# Microcontroller.net
KiCad netlist of a schematic drawn in Altium Designer
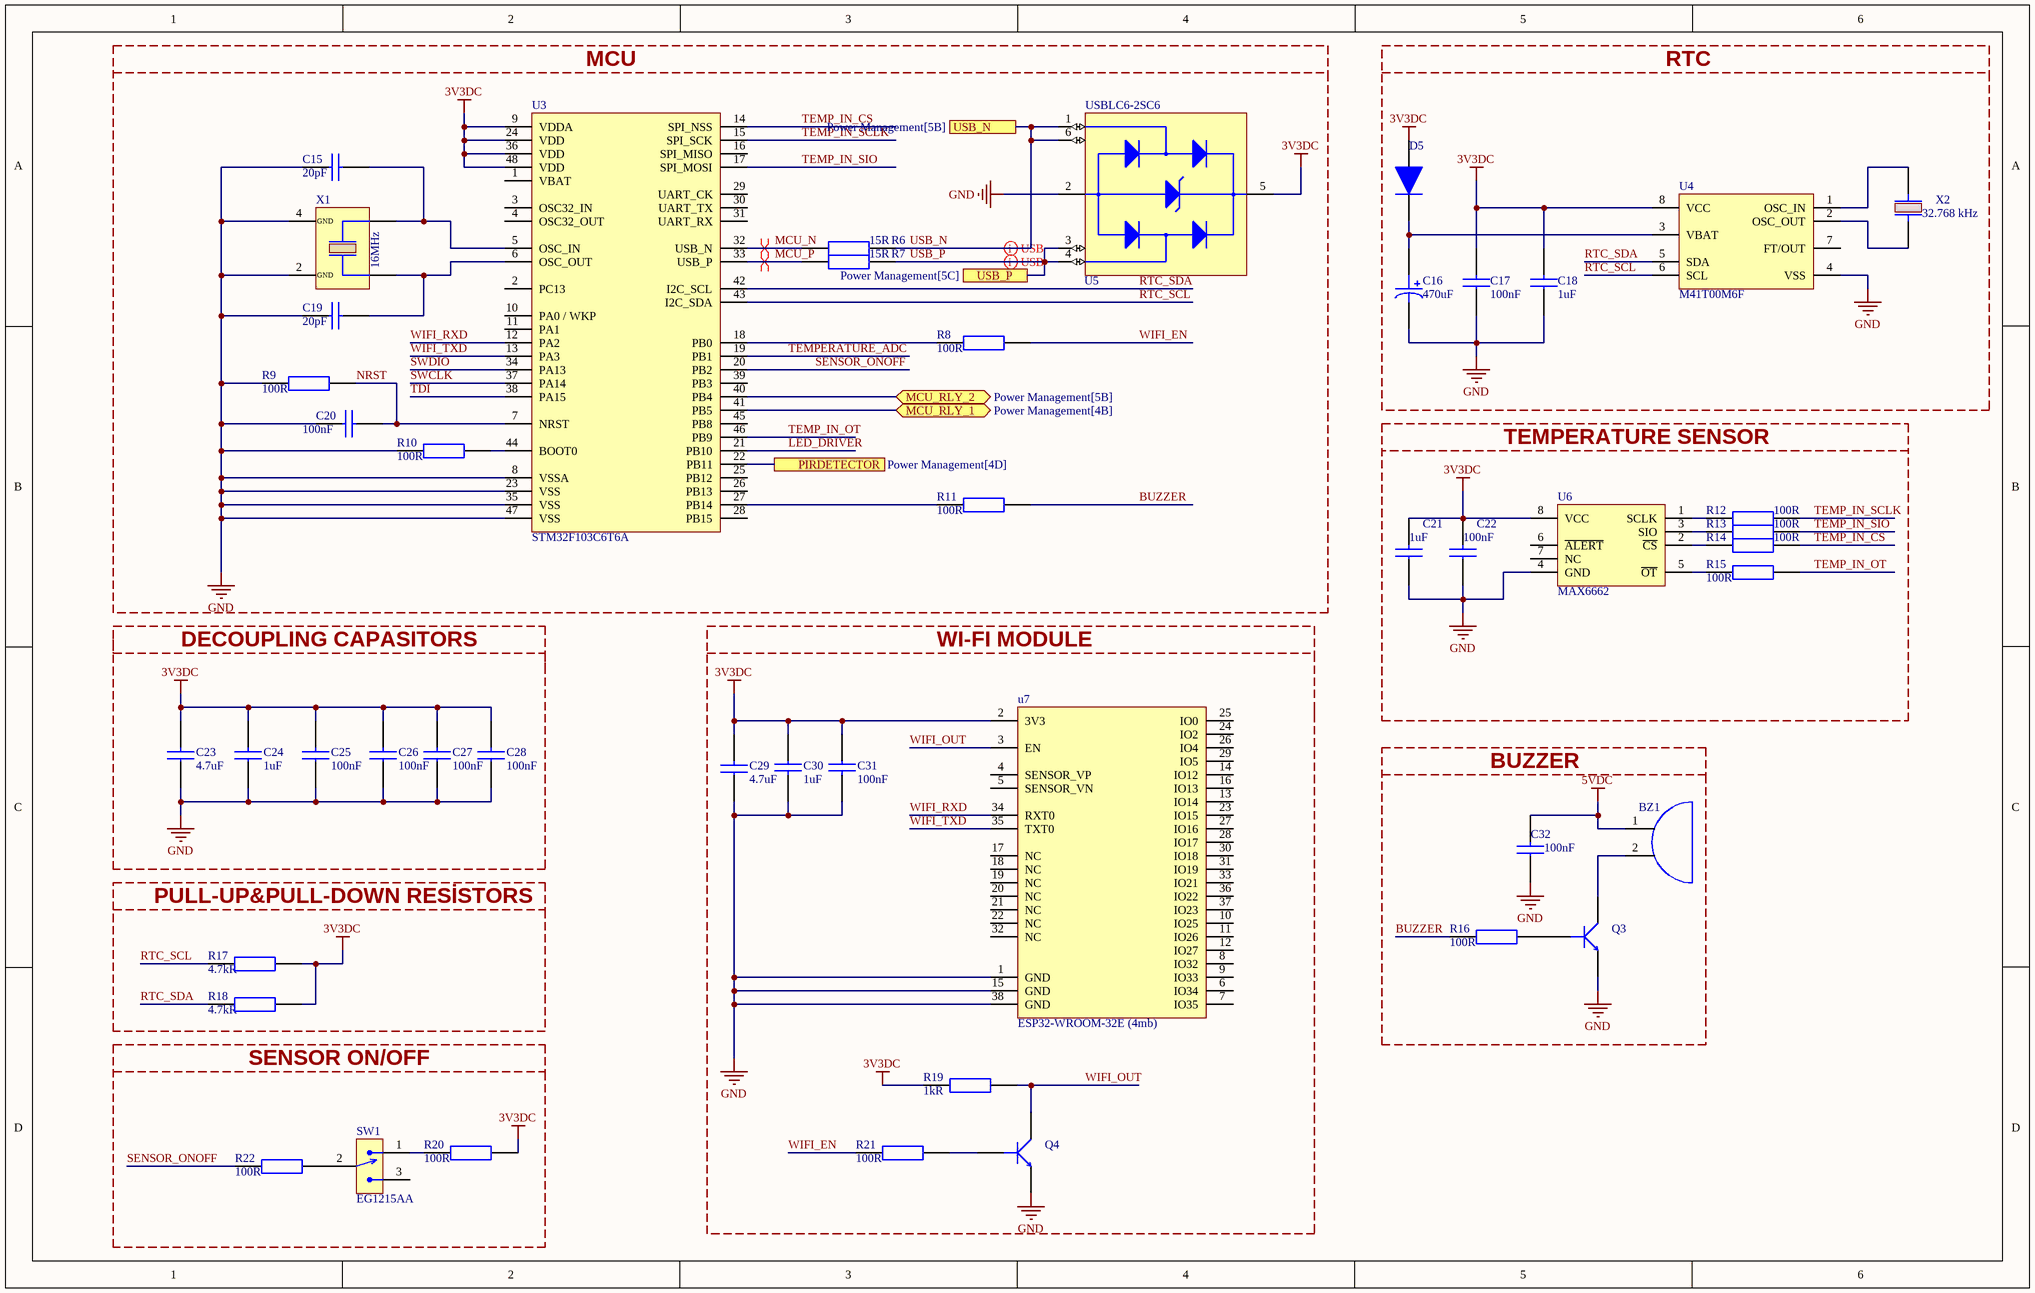
[diagram p0: Microcontroller.SchDoc]

(export (version "E")
  (design (tool "Eeschema 10.0.6"))
  (components
    (comp (ref "BZ1")
      (value "CMI-9605IC-0580T")
      (footprint "CMI-9605IC")
      (description "Audio Buzzer Magnetic 3VDC 7VDC 30mA 5VDC 85dB 2600Hz to 2800Hz Through Hole Pin Box")
      (fields (field (name "MANUFACTURER") "CUI Devices") (field (name "DESIGNED BY") "Mustafa"))
      (libsource (lib "Mustafa_Library") (part "CMI-9605IC-0580T"))
    )
    (comp (ref "C15")
      (value "CL10C200JB8NNNC")
      (footprint "CAP_0603")
      (description "CAP CER 20pF %5 0603 SMD")
      (fields
        (field (name "MANUFACTURER") "Samsung")
        (field (name "TOLERANCE") "5%")
        (field (name "CAPACITANCE") "20pF")
        (field (name "DESIGNED BY") "Mustafa")
      )
      (libsource (lib "Mustafa_Library") (part "CAP CER 20pF 0603"))
    )
    (comp (ref "C16")
      (value "ESH477M050AH4AA")
      (footprint "CAP_RADIAL_D10_P5")
      (description "CAP ALU ELEC 470uF 50V RADIAL")
      (fields
        (field (name "MANUFACTURER") "KEMET")
        (field (name "TOLERANCE") "20%")
        (field (name "CAPACITANCE") "470uF")
        (field (name "DESIGNED BY") "BERK")
      )
      (libsource (lib "Mustafa_Library") (part "CAP ALU ELEC 470uF 50V"))
    )
    (comp (ref "C17")
      (value "CL21B104KBCNNNC")
      (footprint "CAP_0805")
      (description "CAP CER 100nF %10 0805")
      (fields
        (field (name "MANUFACTURER") "Samsung")
        (field (name "TOLERANCE") "10%")
        (field (name "CAPACITANCE") "100nF")
        (field (name "DESIGNED BY") "Mustafa")
      )
      (libsource (lib "Mustafa_Library") (part "CAP CER 100nF 0805"))
    )
    (comp (ref "C18")
      (value "CL21B105KBFNNNE")
      (footprint "CAP_0805")
      (description "CAP CER 1uF %10 0805")
      (fields
        (field (name "MANUFACTURER") "Samsung")
        (field (name "TOLERANCE") "10%")
        (field (name "CAPACITANCE") "1uF")
        (field (name "DESIGNED BY") "Mustafa")
      )
      (libsource (lib "Mustafa_Library") (part "CAP CER 1uF 0805"))
    )
    (comp (ref "C19")
      (value "CL10C200JB8NNNC")
      (footprint "CAP_0603")
      (description "CAP CER 20pF %5 0603 SMD")
      (fields
        (field (name "MANUFACTURER") "Samsung")
        (field (name "TOLERANCE") "5%")
        (field (name "CAPACITANCE") "20pF")
        (field (name "DESIGNED BY") "Mustafa")
      )
      (libsource (lib "Mustafa_Library") (part "CAP CER 20pF 0603"))
    )
    (comp (ref "C20")
      (value "CL21B104KBCNNNC")
      (footprint "CAP_0805")
      (description "CAP CER 100nF %10 0805")
      (fields
        (field (name "MANUFACTURER") "Samsung")
        (field (name "TOLERANCE") "10%")
        (field (name "CAPACITANCE") "100nF")
        (field (name "DESIGNED BY") "Mustafa")
      )
      (libsource (lib "Mustafa_Library") (part "CAP CER 100nF 0805"))
    )
    (comp (ref "C21")
      (value "CL21B105KBFNNNE")
      (footprint "CAP_0805")
      (description "CAP CER 1uF %10 0805")
      (fields
        (field (name "MANUFACTURER") "Samsung")
        (field (name "TOLERANCE") "10%")
        (field (name "CAPACITANCE") "1uF")
        (field (name "DESIGNED BY") "Mustafa")
      )
      (libsource (lib "Mustafa_Library") (part "CAP CER 1uF 0805"))
    )
    (comp (ref "C22")
      (value "CL21B104KBCNNNC")
      (footprint "CAP_0805")
      (description "CAP CER 100nF %10 0805")
      (fields
        (field (name "MANUFACTURER") "Samsung")
        (field (name "TOLERANCE") "10%")
        (field (name "CAPACITANCE") "100nF")
        (field (name "DESIGNED BY") "Mustafa")
      )
      (libsource (lib "Mustafa_Library") (part "CAP CER 100nF 0805"))
    )
    (comp (ref "C23")
      (value "CL21A475KAQNNNE")
      (footprint "CAP_0805")
      (description "CAP CER 4.7uF %10 0805")
      (fields
        (field (name "MANUFACTURER") "Samsung")
        (field (name "TOLERANCE") "10%")
        (field (name "CAPACITANCE") "4.7uF")
        (field (name "DESIGNED BY") "Mustafa")
      )
      (libsource (lib "Mustafa_Library") (part "CAP CER 4.7uF 0805"))
    )
    (comp (ref "C24")
      (value "CL21B105KBFNNNE")
      (footprint "CAP_0805")
      (description "CAP CER 1uF %10 0805")
      (fields
        (field (name "MANUFACTURER") "Samsung")
        (field (name "TOLERANCE") "10%")
        (field (name "CAPACITANCE") "1uF")
        (field (name "DESIGNED BY") "Mustafa")
      )
      (libsource (lib "Mustafa_Library") (part "CAP CER 1uF 0805"))
    )
    (comp (ref "C25")
      (value "CL21B104KBCNNNC")
      (footprint "CAP_0805")
      (description "CAP CER 100nF %10 0805")
      (fields
        (field (name "MANUFACTURER") "Samsung")
        (field (name "TOLERANCE") "10%")
        (field (name "CAPACITANCE") "100nF")
        (field (name "DESIGNED BY") "Mustafa")
      )
      (libsource (lib "Mustafa_Library") (part "CAP CER 100nF 0805"))
    )
    (comp (ref "C26")
      (value "CL21B104KBCNNNC")
      (footprint "CAP_0805")
      (description "CAP CER 100nF %10 0805")
      (fields
        (field (name "MANUFACTURER") "Samsung")
        (field (name "TOLERANCE") "10%")
        (field (name "CAPACITANCE") "100nF")
        (field (name "DESIGNED BY") "Mustafa")
      )
      (libsource (lib "Mustafa_Library") (part "CAP CER 100nF 0805"))
    )
    (comp (ref "C27")
      (value "CL21B104KBCNNNC")
      (footprint "CAP_0805")
      (description "CAP CER 100nF %10 0805")
      (fields
        (field (name "MANUFACTURER") "Samsung")
        (field (name "TOLERANCE") "10%")
        (field (name "CAPACITANCE") "100nF")
        (field (name "DESIGNED BY") "Mustafa")
      )
      (libsource (lib "Mustafa_Library") (part "CAP CER 100nF 0805"))
    )
    (comp (ref "C28")
      (value "CL21B104KBCNNNC")
      (footprint "CAP_0805")
      (description "CAP CER 100nF %10 0805")
      (fields
        (field (name "MANUFACTURER") "Samsung")
        (field (name "TOLERANCE") "10%")
        (field (name "CAPACITANCE") "100nF")
        (field (name "DESIGNED BY") "Mustafa")
      )
      (libsource (lib "Mustafa_Library") (part "CAP CER 100nF 0805"))
    )
    (comp (ref "C29")
      (value "CL21A475KAQNNNE")
      (footprint "CAP_0805")
      (description "CAP CER 4.7uF %10 0805")
      (fields
        (field (name "MANUFACTURER") "Samsung")
        (field (name "TOLERANCE") "10%")
        (field (name "CAPACITANCE") "4.7uF")
        (field (name "DESIGNED BY") "Mustafa")
      )
      (libsource (lib "Mustafa_Library") (part "CAP CER 4.7uF 0805"))
    )
    (comp (ref "C30")
      (value "CL21B105KBFNNNE")
      (footprint "CAP_0805")
      (description "CAP CER 1uF %10 0805")
      (fields
        (field (name "MANUFACTURER") "Samsung")
        (field (name "TOLERANCE") "10%")
        (field (name "CAPACITANCE") "1uF")
        (field (name "DESIGNED BY") "Mustafa")
      )
      (libsource (lib "Mustafa_Library") (part "CAP CER 1uF 0805"))
    )
    (comp (ref "C31")
      (value "CL21B104KBCNNNC")
      (footprint "CAP_0805")
      (description "CAP CER 100nF %10 0805")
      (fields
        (field (name "MANUFACTURER") "Samsung")
        (field (name "TOLERANCE") "10%")
        (field (name "CAPACITANCE") "100nF")
        (field (name "DESIGNED BY") "Mustafa")
      )
      (libsource (lib "Mustafa_Library") (part "CAP CER 100nF 0805"))
    )
    (comp (ref "C32")
      (value "CL21B104KBCNNNC")
      (footprint "CAP_0805")
      (description "CAP CER 100nF %10 0805")
      (fields
        (field (name "MANUFACTURER") "Samsung")
        (field (name "TOLERANCE") "10%")
        (field (name "CAPACITANCE") "100nF")
        (field (name "DESIGNED BY") "Mustafa")
      )
      (libsource (lib "Mustafa_Library") (part "CAP CER 100nF 0805"))
    )
    (comp (ref "D5")
      (value "1N4148WS")
      (footprint "SOD323F")
      (description "Diode, Single, 75 V, 150 mA, 1 V, 4 ns")
      (fields
        (field (name "MANUFACTURER") "ON Semiconductor / Fairchild")
        (field (name "DESIGNED BY") "BERK")
      )
      (libsource (lib "Mustafa_Library") (part "1N4148WS"))
    )
    (comp (ref "Q3")
      (value "MMBT3904-7-F")
      (footprint "SOT-23F")
      (description "Transistor General Purpose BJT NPN 40 Volt 0.2A Automotive 3-Pin SOT-23")
      (fields (field (name "MANUFACTURER") "Diodes Zetex") (field (name "DESIGNED BY") "BERK"))
      (libsource (lib "Mustafa_Library") (part "MMBT3904-7-F"))
    )
    (comp (ref "Q4")
      (value "MMBT3904-7-F")
      (footprint "SOT-23F")
      (description "Transistor General Purpose BJT NPN 40 Volt 0.2A Automotive 3-Pin SOT-23")
      (fields (field (name "MANUFACTURER") "Diodes Zetex") (field (name "DESIGNED BY") "BERK"))
      (libsource (lib "Mustafa_Library") (part "MMBT3904-7-F"))
    )
    (comp (ref "R6")
      (value "RC0603JR-0715RL")
      (footprint "RES_0603")
      (description "RES 15 %5 OHM 0603 SMD")
      (fields
        (field (name "MANUFACTURER") "Yageo")
        (field (name "TOLERANCE") "5%")
        (field (name "RESISTANCE") "15R")
        (field (name "DESIGNED BY") "BERK")
      )
      (libsource (lib "Mustafa_Library") (part "RES 15 OHM 0603"))
    )
    (comp (ref "R7")
      (value "RC0603JR-0715RL")
      (footprint "RES_0603")
      (description "RES 15 %5 OHM 0603 SMD")
      (fields
        (field (name "MANUFACTURER") "Yageo")
        (field (name "TOLERANCE") "5%")
        (field (name "RESISTANCE") "15R")
        (field (name "DESIGNED BY") "BERK")
      )
      (libsource (lib "Mustafa_Library") (part "RES 15 OHM 0603"))
    )
    (comp (ref "R8")
      (value "RC0603JR-07100RL")
      (footprint "RES_0603")
      (description "RES 100 %5 OHM 0603 SMD")
      (fields
        (field (name "MANUFACTURER") "Yageo")
        (field (name "TOLERANCE") "5%")
        (field (name "RESISTANCE") "100R")
        (field (name "DESIGNED BY") "BERK")
      )
      (libsource (lib "Mustafa_Library") (part "RES 100 OHM 0603"))
    )
    (comp (ref "R9")
      (value "RC0603JR-07100RL")
      (footprint "RES_0603")
      (description "RES 100 %5 OHM 0603 SMD")
      (fields
        (field (name "MANUFACTURER") "Yageo")
        (field (name "TOLERANCE") "5%")
        (field (name "RESISTANCE") "100R")
        (field (name "DESIGNED BY") "BERK")
      )
      (libsource (lib "Mustafa_Library") (part "RES 100 OHM 0603"))
    )
    (comp (ref "R10")
      (value "RC0603JR-07100RL")
      (footprint "RES_0603")
      (description "RES 100 %5 OHM 0603 SMD")
      (fields
        (field (name "MANUFACTURER") "Yageo")
        (field (name "TOLERANCE") "5%")
        (field (name "RESISTANCE") "100R")
        (field (name "DESIGNED BY") "BERK")
      )
      (libsource (lib "Mustafa_Library") (part "RES 100 OHM 0603"))
    )
    (comp (ref "R11")
      (value "RC0603JR-07100RL")
      (footprint "RES_0603")
      (description "RES 100 %5 OHM 0603 SMD")
      (fields
        (field (name "MANUFACTURER") "Yageo")
        (field (name "TOLERANCE") "5%")
        (field (name "RESISTANCE") "100R")
        (field (name "DESIGNED BY") "BERK")
      )
      (libsource (lib "Mustafa_Library") (part "RES 100 OHM 0603"))
    )
    (comp (ref "R12")
      (value "RC0603JR-07100RL")
      (footprint "RES_0603")
      (description "RES 100 %5 OHM 0603 SMD")
      (fields
        (field (name "MANUFACTURER") "Yageo")
        (field (name "TOLERANCE") "5%")
        (field (name "RESISTANCE") "100R")
        (field (name "DESIGNED BY") "BERK")
      )
      (libsource (lib "Mustafa_Library") (part "RES 100 OHM 0603"))
    )
    (comp (ref "R13")
      (value "RC0603JR-07100RL")
      (footprint "RES_0603")
      (description "RES 100 %5 OHM 0603 SMD")
      (fields
        (field (name "MANUFACTURER") "Yageo")
        (field (name "TOLERANCE") "5%")
        (field (name "RESISTANCE") "100R")
        (field (name "DESIGNED BY") "BERK")
      )
      (libsource (lib "Mustafa_Library") (part "RES 100 OHM 0603"))
    )
    (comp (ref "R14")
      (value "RC0603JR-07100RL")
      (footprint "RES_0603")
      (description "RES 100 %5 OHM 0603 SMD")
      (fields
        (field (name "MANUFACTURER") "Yageo")
        (field (name "TOLERANCE") "5%")
        (field (name "RESISTANCE") "100R")
        (field (name "DESIGNED BY") "BERK")
      )
      (libsource (lib "Mustafa_Library") (part "RES 100 OHM 0603"))
    )
    (comp (ref "R15")
      (value "RC0603JR-07100RL")
      (footprint "RES_0603")
      (description "RES 100 %5 OHM 0603 SMD")
      (fields
        (field (name "MANUFACTURER") "Yageo")
        (field (name "TOLERANCE") "5%")
        (field (name "RESISTANCE") "100R")
        (field (name "DESIGNED BY") "BERK")
      )
      (libsource (lib "Mustafa_Library") (part "RES 100 OHM 0603"))
    )
    (comp (ref "R16")
      (value "RC0603JR-07100RL")
      (footprint "RES_0603")
      (description "RES 100 %5 OHM 0603 SMD")
      (fields
        (field (name "MANUFACTURER") "Yageo")
        (field (name "TOLERANCE") "5%")
        (field (name "RESISTANCE") "100R")
        (field (name "DESIGNED BY") "BERK")
      )
      (libsource (lib "Mustafa_Library") (part "RES 100 OHM 0603"))
    )
    (comp (ref "R17")
      (value "RC0603JR-074K7L")
      (footprint "RES_0603")
      (description "RES 4K7 %5 OHM 0603 SMD")
      (fields
        (field (name "MANUFACTURER") "Yageo")
        (field (name "TOLERANCE") "5%")
        (field (name "RESISTANCE") "4.7kR")
        (field (name "DESIGNED BY") "BERK")
      )
      (libsource (lib "Mustafa_Library") (part "RES 4K7 OHM 0603"))
    )
    (comp (ref "R18")
      (value "RC0603JR-074K7L")
      (footprint "RES_0603")
      (description "RES 4K7 %5 OHM 0603 SMD")
      (fields
        (field (name "MANUFACTURER") "Yageo")
        (field (name "TOLERANCE") "5%")
        (field (name "RESISTANCE") "4.7kR")
        (field (name "DESIGNED BY") "BERK")
      )
      (libsource (lib "Mustafa_Library") (part "RES 4K7 OHM 0603"))
    )
    (comp (ref "R19")
      (value "RC0603FR-0710KL")
      (footprint "RES_0603")
      (description "RES 1K %1 OHM 0603 SMD")
      (fields
        (field (name "MANUFACTURER") "Yageo")
        (field (name "MANUFACTURER PART NUMBER") "RC0603JR-071KL")
        (field (name "RESISTANCE") "1kR")
        (field (name "DESIGNED BY") "BERK")
      )
      (libsource (lib "Mustafa_Library") (part "RES 1K OHM 0603"))
    )
    (comp (ref "R20")
      (value "RC0603JR-07100RL")
      (footprint "RES_0603")
      (description "RES 100 %5 OHM 0603 SMD")
      (fields
        (field (name "MANUFACTURER") "Yageo")
        (field (name "TOLERANCE") "5%")
        (field (name "RESISTANCE") "100R")
        (field (name "DESIGNED BY") "BERK")
      )
      (libsource (lib "Mustafa_Library") (part "RES 100 OHM 0603"))
    )
    (comp (ref "R21")
      (value "RC0603JR-07100RL")
      (footprint "RES_0603")
      (description "RES 100 %5 OHM 0603 SMD")
      (fields
        (field (name "MANUFACTURER") "Yageo")
        (field (name "TOLERANCE") "5%")
        (field (name "RESISTANCE") "100R")
        (field (name "DESIGNED BY") "BERK")
      )
      (libsource (lib "Mustafa_Library") (part "RES 100 OHM 0603"))
    )
    (comp (ref "R22")
      (value "RC0603JR-07100RL")
      (footprint "RES_0603")
      (description "RES 100 %5 OHM 0603 SMD")
      (fields
        (field (name "MANUFACTURER") "Yageo")
        (field (name "TOLERANCE") "5%")
        (field (name "RESISTANCE") "100R")
        (field (name "DESIGNED BY") "BERK")
      )
      (libsource (lib "Mustafa_Library") (part "RES 100 OHM 0603"))
    )
    (comp (ref "SW1")
      (value "EG1215AA")
      (footprint "EG1215AA")
      (description "SWITCH SLIDE SPDT 25MA 24V")
      (fields (field (name "MANUFACTURER") "E-Switch") (field (name "DESIGNED BY") "Mustafa"))
      (libsource (lib "Mustafa_Library") (part "EG1215AA"))
    )
    (comp (ref "U3")
      (value "STM32F103C6T6A")
      (footprint "LQFP-48")
      (description "MCU 32-bit STM32F ARM Cortex M3 RISC 32KB Flash 2.5V/3.3V 48-Pin LQFP T/R")
      (fields (field (name "MANUFACTURER") "STMicroelectronics") (field (name "DESIGNED BY") "Mustafa"))
      (libsource (lib "Mustafa_Library") (part "STM32F103C6T6A"))
    )
    (comp (ref "U4")
      (value "M41T00M6F")
      (footprint "SOIC-8")
      (description "Real-time Clocks Clock/Calendar I2C, 2-Wire Serial 70uA @ 2V ~ 5.5V SOIC-8_150mil RoHS")
      (fields (field (name "MANUFACTURER") "STMicroelectronics") (field (name "DESIGNED BY") "Mustafa"))
      (libsource (lib "Mustafa_Library") (part "M41T00M6F"))
    )
    (comp (ref "U5")
      (value "USBLC6-2SC6")
      (footprint "SOT23-6L")
      (description "TVS DIODE 5.25V 17V SOT23-6")
      (fields (field (name "MANUFACTURER") "STMicroelectronics") (field (name "DESIGNED BY") "BERK"))
      (libsource (lib "Mustafa_Library") (part "USB PROTECTION"))
    )
    (comp (ref "U6")
      (value "MAX6662")
      (footprint "SOIC-8")
      (description "SENSOR TEMPERATURE SPI 8SOIC")
      (fields
        (field (name "MANUFACTURER") "Maxim")
        (field (name "MANUFACTURER PART NUMBER") "MAX6662MSA+")
        (field (name "DESIGNED BY") "Mustafa")
      )
      (libsource (lib "Mustafa_Library") (part "MAX6662"))
    )
    (comp (ref "u7")
      (value "ESP32-WROOM-32E (4mb)")
      (footprint "ESP32-32")
      (description "SMD module, ESP32-D0WD-V3, ESP32 ECO V3, 4 MB SPI flash, PCB antenna")
      (fields
        (field (name "MANUFACTURER") "Espressif Systems")
        (field (name "MANUFACTURER PART NUMBER") "ESP32-WROOM-32E(M113EH3200PH3Q0)")
        (field (name "DESIGNED BY") "Mustafa")
      )
      (libsource (lib "Mustafa_Library") (part "ESP32-WROOM-32E (4mb)"))
    )
    (comp (ref "X1")
      (value "ECS-160-20-30B-TR")
      (footprint "ECS")
      (description "CRYSTAL 16.0000MHZ 20PF SMD")
      (fields
        (field (name "MANUFACTURER") "ECS International")
        (field (name "TOLERANCE") "50ppm")
        (field (name "FREQUENCY") "16MHz")
        (field (name "DESIGNED BY") "Mustafa")
      )
      (libsource (lib "Mustafa_Library") (part "CRYSTAL 16MHz"))
    )
    (comp (ref "X2")
      (value "ABS05-32.768KHZ-T")
      (footprint "ABS05")
      (description "Crystal, 32.768 kHz, SMD, 1.6mm x 1mm, 12.5 pF, 20 ppm, ABS05 Series")
      (fields
        (field (name "MANUFACTURER") "Abracon")
        (field (name "TOLERANCE") "20ppm")
        (field (name "OPERATING FREQUENCY") "32.768 kHz")
        (field (name "DESIGNED BY") "Mustafa")
      )
      (libsource (lib "Mustafa_Library") (part "CRYSTAL 32768kHZ"))
    )
  )
  (nets
    (net (code "1") (name "/BUZZER") (class "Default")
      (node (ref "R11") (pin "2") (pinfunction "2_2") (pintype "passive"))
      (node (ref "R16") (pin "1") (pinfunction "1_1") (pintype "passive"))
    )
    (net (code "2") (name "/LED_DRIVER") (class "Default")
      (node (ref "U3") (pin "21") (pinfunction "PB10_21") (pintype "passive"))
    )
    (net (code "3") (name "/MCU_N") (class "Default")
      (node (ref "R6") (pin "1") (pinfunction "1_1") (pintype "passive"))
      (node (ref "U3") (pin "32") (pinfunction "USB_N_32") (pintype "passive"))
    )
    (net (code "4") (name "/MCU_P") (class "Default")
      (node (ref "R7") (pin "1") (pinfunction "1_1") (pintype "passive"))
      (node (ref "U3") (pin "33") (pinfunction "USB_P_33") (pintype "passive"))
    )
    (net (code "5") (name "/MCU_RLY_1") (class "Default")
      (node (ref "U3") (pin "41") (pinfunction "PB5_41") (pintype "passive"))
    )
    (net (code "6") (name "/MCU_RLY_2") (class "Default")
      (node (ref "U3") (pin "40") (pinfunction "PB4_40") (pintype "passive"))
    )
    (net (code "7") (name "/NRST") (class "Default")
      (node (ref "C20") (pin "2") (pinfunction "2_2") (pintype "passive"))
      (node (ref "R9") (pin "2") (pinfunction "2_2") (pintype "passive"))
      (node (ref "U3") (pin "7") (pinfunction "NRST_7") (pintype "passive"))
    )
    (net (code "8") (name "/PIRDETECTOR") (class "Default")
      (node (ref "U3") (pin "22") (pinfunction "PB11_22") (pintype "passive"))
    )
    (net (code "9") (name "/RTC_SCL") (class "Default")
      (node (ref "R17") (pin "1") (pinfunction "1_1") (pintype "passive"))
      (node (ref "U3") (pin "43") (pinfunction "I2C_SDA_43") (pintype "passive"))
      (node (ref "U4") (pin "6") (pinfunction "SCL_6") (pintype "passive"))
    )
    (net (code "10") (name "/RTC_SDA") (class "Default")
      (node (ref "R18") (pin "1") (pinfunction "1_1") (pintype "passive"))
      (node (ref "U3") (pin "42") (pinfunction "I2C_SCL_42") (pintype "passive"))
      (node (ref "U4") (pin "5") (pinfunction "SDA_5") (pintype "passive"))
    )
    (net (code "11") (name "/SENSOR_ONOFF") (class "Default")
      (node (ref "R22") (pin "1") (pinfunction "1_1") (pintype "passive"))
      (node (ref "U3") (pin "20") (pinfunction "PB2_20") (pintype "passive"))
    )
    (net (code "12") (name "/SWCLK") (class "Default")
      (node (ref "U3") (pin "37") (pinfunction "PA14_37") (pintype "passive"))
    )
    (net (code "13") (name "/SWDIO") (class "Default")
      (node (ref "U3") (pin "34") (pinfunction "PA13_34") (pintype "passive"))
    )
    (net (code "14") (name "/TDI") (class "Default")
      (node (ref "U3") (pin "38") (pinfunction "PA15_38") (pintype "passive"))
    )
    (net (code "15") (name "/TEMPERATURE_ADC") (class "Default")
      (node (ref "U3") (pin "19") (pinfunction "PB1_19") (pintype "passive"))
    )
    (net (code "16") (name "/TEMP_IN_CS") (class "Default")
      (node (ref "R14") (pin "2") (pinfunction "2_2") (pintype "passive"))
      (node (ref "U3") (pin "14") (pinfunction "SPI_NSS_14") (pintype "passive"))
    )
    (net (code "17") (name "/TEMP_IN_OT") (class "Default")
      (node (ref "R15") (pin "2") (pinfunction "2_2") (pintype "passive"))
      (node (ref "U3") (pin "46") (pinfunction "PB9_46") (pintype "passive"))
    )
    (net (code "18") (name "/TEMP_IN_SCLK") (class "Default")
      (node (ref "R12") (pin "2") (pinfunction "2_2") (pintype "passive"))
      (node (ref "U3") (pin "15") (pinfunction "SPI_SCK_15") (pintype "passive"))
    )
    (net (code "19") (name "/TEMP_IN_SIO") (class "Default")
      (node (ref "R13") (pin "2") (pinfunction "2_2") (pintype "passive"))
      (node (ref "U3") (pin "17") (pinfunction "SPI_MOSI_17") (pintype "passive"))
    )
    (net (code "20") (name "/USB_N") (class "Default")
      (node (ref "R6") (pin "2") (pinfunction "2_2") (pintype "passive"))
      (node (ref "U5") (pin "1") (pinfunction "I/O1_1") (pintype "bidirectional"))
      (node (ref "U5") (pin "6") (pinfunction "I/O1_6") (pintype "bidirectional"))
    )
    (net (code "21") (name "/USB_P") (class "Default")
      (node (ref "R7") (pin "2") (pinfunction "2_2") (pintype "passive"))
      (node (ref "U5") (pin "3") (pinfunction "I/O2_3") (pintype "bidirectional"))
      (node (ref "U5") (pin "4") (pinfunction "I/O2_4") (pintype "bidirectional"))
    )
    (net (code "22") (name "/WIFI_EN") (class "Default")
      (node (ref "R21") (pin "1") (pinfunction "1_1") (pintype "passive"))
      (node (ref "R8") (pin "2") (pinfunction "2_2") (pintype "passive"))
    )
    (net (code "23") (name "/WIFI_OUT") (class "Default")
      (node (ref "Q4") (pin "3") (pinfunction "C_3") (pintype "power_in"))
      (node (ref "R19") (pin "2") (pinfunction "2_2") (pintype "passive"))
      (node (ref "u7") (pin "3") (pinfunction "EN_3") (pintype "passive"))
    )
    (net (code "24") (name "/WIFI_RXD") (class "Default")
      (node (ref "U3") (pin "12") (pinfunction "PA2_12") (pintype "passive"))
      (node (ref "u7") (pin "34") (pinfunction "RXT0_34") (pintype "passive"))
    )
    (net (code "25") (name "/WIFI_TXD") (class "Default")
      (node (ref "U3") (pin "13") (pinfunction "PA3_13") (pintype "passive"))
      (node (ref "u7") (pin "35") (pinfunction "TXT0_35") (pintype "passive"))
    )
    (net (code "26") (name "3V3DC") (class "Default")
      (node (ref "C17") (pin "2") (pinfunction "2_2") (pintype "passive"))
      (node (ref "C18") (pin "2") (pinfunction "2_2") (pintype "passive"))
      (node (ref "C21") (pin "2") (pinfunction "2_2") (pintype "passive"))
      (node (ref "C22") (pin "2") (pinfunction "2_2") (pintype "passive"))
      (node (ref "C23") (pin "2") (pinfunction "2_2") (pintype "passive"))
      (node (ref "C24") (pin "2") (pinfunction "2_2") (pintype "passive"))
      (node (ref "C25") (pin "2") (pinfunction "2_2") (pintype "passive"))
      (node (ref "C26") (pin "2") (pinfunction "2_2") (pintype "passive"))
      (node (ref "C27") (pin "2") (pinfunction "2_2") (pintype "passive"))
      (node (ref "C28") (pin "2") (pinfunction "2_2") (pintype "passive"))
      (node (ref "C29") (pin "2") (pinfunction "2_2") (pintype "passive"))
      (node (ref "C30") (pin "1") (pinfunction "1_1") (pintype "passive"))
      (node (ref "C31") (pin "1") (pinfunction "1_1") (pintype "passive"))
      (node (ref "D5") (pin "2") (pinfunction "2_2") (pintype "power_in"))
      (node (ref "R17") (pin "2") (pinfunction "2_2") (pintype "passive"))
      (node (ref "R18") (pin "2") (pinfunction "2_2") (pintype "passive"))
      (node (ref "R19") (pin "1") (pinfunction "1_1") (pintype "passive"))
      (node (ref "R20") (pin "2") (pinfunction "2_2") (pintype "passive"))
      (node (ref "U3") (pin "24") (pinfunction "VDD_24") (pintype "passive"))
      (node (ref "U3") (pin "36") (pinfunction "VDD_36") (pintype "passive"))
      (node (ref "U3") (pin "48") (pinfunction "VDD_48") (pintype "passive"))
      (node (ref "U3") (pin "9") (pinfunction "VDDA_9") (pintype "passive"))
      (node (ref "U4") (pin "8") (pinfunction "VCC_8") (pintype "passive"))
      (node (ref "U5") (pin "5") (pinfunction "VBUS_5") (pintype "power_in"))
      (node (ref "U6") (pin "8") (pinfunction "VCC_8") (pintype "passive"))
      (node (ref "u7") (pin "2") (pinfunction "3V3_2") (pintype "passive"))
    )
    (net (code "27") (name "5VDC") (class "Default")
      (node (ref "BZ1") (pin "1") (pinfunction "1_1") (pintype "passive"))
      (node (ref "C32") (pin "2") (pinfunction "2_2") (pintype "passive"))
    )
    (net (code "28") (name "GND") (class "Default")
      (node (ref "C15") (pin "1") (pinfunction "1_1") (pintype "passive"))
      (node (ref "C16") (pin "2") (pinfunction "2_2") (pintype "passive"))
      (node (ref "C17") (pin "1") (pinfunction "1_1") (pintype "passive"))
      (node (ref "C18") (pin "1") (pinfunction "1_1") (pintype "passive"))
      (node (ref "C19") (pin "1") (pinfunction "1_1") (pintype "passive"))
      (node (ref "C20") (pin "1") (pinfunction "1_1") (pintype "passive"))
      (node (ref "C21") (pin "1") (pinfunction "1_1") (pintype "passive"))
      (node (ref "C22") (pin "1") (pinfunction "1_1") (pintype "passive"))
      (node (ref "C23") (pin "1") (pinfunction "1_1") (pintype "passive"))
      (node (ref "C24") (pin "1") (pinfunction "1_1") (pintype "passive"))
      (node (ref "C25") (pin "1") (pinfunction "1_1") (pintype "passive"))
      (node (ref "C26") (pin "1") (pinfunction "1_1") (pintype "passive"))
      (node (ref "C27") (pin "1") (pinfunction "1_1") (pintype "passive"))
      (node (ref "C28") (pin "1") (pinfunction "1_1") (pintype "passive"))
      (node (ref "C29") (pin "1") (pinfunction "1_1") (pintype "passive"))
      (node (ref "C30") (pin "2") (pinfunction "2_2") (pintype "passive"))
      (node (ref "C31") (pin "2") (pinfunction "2_2") (pintype "passive"))
      (node (ref "C32") (pin "1") (pinfunction "1_1") (pintype "passive"))
      (node (ref "Q3") (pin "2") (pinfunction "E_2") (pintype "power_in"))
      (node (ref "Q4") (pin "2") (pinfunction "E_2") (pintype "power_in"))
      (node (ref "R10") (pin "1") (pinfunction "1_1") (pintype "passive"))
      (node (ref "R9") (pin "1") (pinfunction "1_1") (pintype "passive"))
      (node (ref "U3") (pin "23") (pinfunction "VSS_23") (pintype "passive"))
      (node (ref "U3") (pin "35") (pinfunction "VSS_35") (pintype "passive"))
      (node (ref "U3") (pin "47") (pinfunction "VSS_47") (pintype "passive"))
      (node (ref "U3") (pin "8") (pinfunction "VSSA_8") (pintype "passive"))
      (node (ref "U4") (pin "4") (pinfunction "VSS_4") (pintype "passive"))
      (node (ref "U5") (pin "2") (pinfunction "GND_2") (pintype "power_in"))
      (node (ref "U6") (pin "4") (pinfunction "GND_4") (pintype "passive"))
      (node (ref "X1") (pin "2") (pinfunction "GND_2") (pintype "passive"))
      (node (ref "X1") (pin "4") (pinfunction "GND_4") (pintype "passive"))
      (node (ref "u7") (pin "1") (pinfunction "GND_1") (pintype "passive"))
      (node (ref "u7") (pin "15") (pinfunction "GND_15") (pintype "passive"))
      (node (ref "u7") (pin "38") (pinfunction "GND_38") (pintype "passive"))
    )
    (net (code "29") (name "Net-(Q3-B)") (class "Default")
      (node (ref "Q3") (pin "1") (pinfunction "B_1") (pintype "power_in"))
      (node (ref "R16") (pin "2") (pinfunction "2_2") (pintype "passive"))
    )
    (net (code "30") (name "Net-(Q3-C)") (class "Default")
      (node (ref "BZ1") (pin "2") (pinfunction "2_2") (pintype "passive"))
      (node (ref "Q3") (pin "3") (pinfunction "C_3") (pintype "power_in"))
    )
    (net (code "31") (name "Net-(Q4-B)") (class "Default")
      (node (ref "Q4") (pin "1") (pinfunction "B_1") (pintype "power_in"))
      (node (ref "R21") (pin "2") (pinfunction "2_2") (pintype "passive"))
    )
    (net (code "32") (name "Net-(R20-Pad1)") (class "Default")
      (node (ref "R20") (pin "1") (pinfunction "1_1") (pintype "passive"))
      (node (ref "SW1") (pin "1") (pinfunction "1_1") (pintype "passive"))
    )
    (net (code "33") (name "Net-(R22-Pad2)") (class "Default")
      (node (ref "R22") (pin "2") (pinfunction "2_2") (pintype "passive"))
      (node (ref "SW1") (pin "2") (pinfunction "2_2") (pintype "passive"))
    )
    (net (code "34") (name "Net-(U3-BOOT0)") (class "Default")
      (node (ref "R10") (pin "2") (pinfunction "2_2") (pintype "passive"))
      (node (ref "U3") (pin "44") (pinfunction "BOOT0_44") (pintype "passive"))
    )
    (net (code "35") (name "Net-(U3-OSC_IN)") (class "Default")
      (node (ref "C15") (pin "2") (pinfunction "2_2") (pintype "passive"))
      (node (ref "U3") (pin "5") (pinfunction "OSC_IN_5") (pintype "passive"))
      (node (ref "X1") (pin "3") (pinfunction "3_3") (pintype "passive"))
    )
    (net (code "36") (name "Net-(U3-OSC_OUT)") (class "Default")
      (node (ref "C19") (pin "2") (pinfunction "2_2") (pintype "passive"))
      (node (ref "U3") (pin "6") (pinfunction "OSC_OUT_6") (pintype "passive"))
      (node (ref "X1") (pin "1") (pinfunction "1_1") (pintype "passive"))
    )
    (net (code "37") (name "Net-(U3-PB0)") (class "Default")
      (node (ref "R8") (pin "1") (pinfunction "1_1") (pintype "passive"))
      (node (ref "U3") (pin "18") (pinfunction "PB0_18") (pintype "passive"))
    )
    (net (code "38") (name "Net-(U3-PB14)") (class "Default")
      (node (ref "R11") (pin "1") (pinfunction "1_1") (pintype "passive"))
      (node (ref "U3") (pin "27") (pinfunction "PB14_27") (pintype "passive"))
    )
    (net (code "39") (name "Net-(U4-OSC_IN)") (class "Default")
      (node (ref "U4") (pin "1") (pinfunction "OSC_IN_1") (pintype "passive"))
      (node (ref "X2") (pin "2") (pinfunction "2_2") (pintype "passive"))
    )
    (net (code "40") (name "Net-(U4-OSC_OUT)") (class "Default")
      (node (ref "U4") (pin "2") (pinfunction "OSC_OUT_2") (pintype "passive"))
      (node (ref "X2") (pin "1") (pinfunction "1_1") (pintype "passive"))
    )
    (net (code "41") (name "Net-(U4-VBAT)") (class "Default")
      (node (ref "C16") (pin "1") (pinfunction "1_1") (pintype "passive"))
      (node (ref "D5") (pin "1") (pinfunction "1_1") (pintype "power_in"))
      (node (ref "U4") (pin "3") (pinfunction "VBAT_3") (pintype "passive"))
    )
    (net (code "42") (name "Net-(U6-SCLK)") (class "Default")
      (node (ref "R12") (pin "1") (pinfunction "1_1") (pintype "passive"))
      (node (ref "U6") (pin "1") (pinfunction "SCLK_1") (pintype "passive"))
    )
    (net (code "43") (name "Net-(U6-SIO)") (class "Default")
      (node (ref "R13") (pin "1") (pinfunction "1_1") (pintype "passive"))
      (node (ref "U6") (pin "3") (pinfunction "SIO_3") (pintype "passive"))
    )
    (net (code "44") (name "Net-(U6-~{CS})") (class "Default")
      (node (ref "R14") (pin "1") (pinfunction "1_1") (pintype "passive"))
      (node (ref "U6") (pin "2") (pinfunction "~{CS}_2") (pintype "passive"))
    )
    (net (code "45") (name "Net-(U6-~{OT})") (class "Default")
      (node (ref "R15") (pin "1") (pinfunction "1_1") (pintype "passive"))
      (node (ref "U6") (pin "5") (pinfunction "~{OT}_5") (pintype "passive"))
    )
    (net (code "46") (name "unconnected-(SW1-Pad3)") (class "Default")
      (node (ref "SW1") (pin "3") (pinfunction "3_3") (pintype "passive"))
    )
    (net (code "47") (name "unconnected-(U3-OSC32_IN-Pad3)") (class "Default")
      (node (ref "U3") (pin "3") (pinfunction "OSC32_IN_3") (pintype "passive"))
    )
    (net (code "48") (name "unconnected-(U3-OSC32_OUT-Pad4)") (class "Default")
      (node (ref "U3") (pin "4") (pinfunction "OSC32_OUT_4") (pintype "passive"))
    )
    (net (code "49") (name "unconnected-(U3-PA0_{slash}_WKP-Pad10)") (class "Default")
      (node (ref "U3") (pin "10") (pinfunction "PA0_/_WKP_10") (pintype "passive"))
    )
    (net (code "50") (name "unconnected-(U3-PA1-Pad11)") (class "Default")
      (node (ref "U3") (pin "11") (pinfunction "PA1_11") (pintype "passive"))
    )
    (net (code "51") (name "unconnected-(U3-PB3-Pad39)") (class "Default")
      (node (ref "U3") (pin "39") (pinfunction "PB3_39") (pintype "passive"))
    )
    (net (code "52") (name "unconnected-(U3-PB8-Pad45)") (class "Default")
      (node (ref "U3") (pin "45") (pinfunction "PB8_45") (pintype "passive"))
    )
    (net (code "53") (name "unconnected-(U3-PB12-Pad25)") (class "Default")
      (node (ref "U3") (pin "25") (pinfunction "PB12_25") (pintype "passive"))
    )
    (net (code "54") (name "unconnected-(U3-PB13-Pad26)") (class "Default")
      (node (ref "U3") (pin "26") (pinfunction "PB13_26") (pintype "passive"))
    )
    (net (code "55") (name "unconnected-(U3-PB15-Pad28)") (class "Default")
      (node (ref "U3") (pin "28") (pinfunction "PB15_28") (pintype "passive"))
    )
    (net (code "56") (name "unconnected-(U3-PC13-Pad2)") (class "Default")
      (node (ref "U3") (pin "2") (pinfunction "PC13_2") (pintype "passive"))
    )
    (net (code "57") (name "unconnected-(U3-SPI_MISO-Pad16)") (class "Default")
      (node (ref "U3") (pin "16") (pinfunction "SPI_MISO_16") (pintype "passive"))
    )
    (net (code "58") (name "unconnected-(U3-UART_CK-Pad29)") (class "Default")
      (node (ref "U3") (pin "29") (pinfunction "UART_CK_29") (pintype "passive"))
    )
    (net (code "59") (name "unconnected-(U3-UART_RX-Pad31)") (class "Default")
      (node (ref "U3") (pin "31") (pinfunction "UART_RX_31") (pintype "passive"))
    )
    (net (code "60") (name "unconnected-(U3-UART_TX-Pad30)") (class "Default")
      (node (ref "U3") (pin "30") (pinfunction "UART_TX_30") (pintype "passive"))
    )
    (net (code "61") (name "unconnected-(U3-VBAT-Pad1)") (class "Default")
      (node (ref "U3") (pin "1") (pinfunction "VBAT_1") (pintype "passive"))
    )
    (net (code "62") (name "unconnected-(U4-FT{slash}OUT-Pad7)") (class "Default")
      (node (ref "U4") (pin "7") (pinfunction "FT/OUT_7") (pintype "passive"))
    )
    (net (code "63") (name "unconnected-(U6-NC-Pad7)") (class "Default")
      (node (ref "U6") (pin "7") (pinfunction "NC_7") (pintype "passive"))
    )
    (net (code "64") (name "unconnected-(U6-~{ALERT}-Pad6)") (class "Default")
      (node (ref "U6") (pin "6") (pinfunction "~{ALERT}_6") (pintype "passive"))
    )
    (net (code "65") (name "unconnected-(u7-IO0-Pad25)") (class "Default")
      (node (ref "u7") (pin "25") (pinfunction "IO0_25") (pintype "passive"))
    )
    (net (code "66") (name "unconnected-(u7-IO2-Pad24)") (class "Default")
      (node (ref "u7") (pin "24") (pinfunction "IO2_24") (pintype "passive"))
    )
    (net (code "67") (name "unconnected-(u7-IO4-Pad26)") (class "Default")
      (node (ref "u7") (pin "26") (pinfunction "IO4_26") (pintype "passive"))
    )
    (net (code "68") (name "unconnected-(u7-IO5-Pad29)") (class "Default")
      (node (ref "u7") (pin "29") (pinfunction "IO5_29") (pintype "passive"))
    )
    (net (code "69") (name "unconnected-(u7-IO12-Pad14)") (class "Default")
      (node (ref "u7") (pin "14") (pinfunction "IO12_14") (pintype "passive"))
    )
    (net (code "70") (name "unconnected-(u7-IO13-Pad16)") (class "Default")
      (node (ref "u7") (pin "16") (pinfunction "IO13_16") (pintype "passive"))
    )
    (net (code "71") (name "unconnected-(u7-IO14-Pad13)") (class "Default")
      (node (ref "u7") (pin "13") (pinfunction "IO14_13") (pintype "passive"))
    )
    (net (code "72") (name "unconnected-(u7-IO15-Pad23)") (class "Default")
      (node (ref "u7") (pin "23") (pinfunction "IO15_23") (pintype "passive"))
    )
    (net (code "73") (name "unconnected-(u7-IO16-Pad27)") (class "Default")
      (node (ref "u7") (pin "27") (pinfunction "IO16_27") (pintype "passive"))
    )
    (net (code "74") (name "unconnected-(u7-IO17-Pad28)") (class "Default")
      (node (ref "u7") (pin "28") (pinfunction "IO17_28") (pintype "passive"))
    )
    (net (code "75") (name "unconnected-(u7-IO18-Pad30)") (class "Default")
      (node (ref "u7") (pin "30") (pinfunction "IO18_30") (pintype "passive"))
    )
    (net (code "76") (name "unconnected-(u7-IO19-Pad31)") (class "Default")
      (node (ref "u7") (pin "31") (pinfunction "IO19_31") (pintype "passive"))
    )
    (net (code "77") (name "unconnected-(u7-IO21-Pad33)") (class "Default")
      (node (ref "u7") (pin "33") (pinfunction "IO21_33") (pintype "passive"))
    )
    (net (code "78") (name "unconnected-(u7-IO22-Pad36)") (class "Default")
      (node (ref "u7") (pin "36") (pinfunction "IO22_36") (pintype "passive"))
    )
    (net (code "79") (name "unconnected-(u7-IO23-Pad37)") (class "Default")
      (node (ref "u7") (pin "37") (pinfunction "IO23_37") (pintype "passive"))
    )
    (net (code "80") (name "unconnected-(u7-IO25-Pad10)") (class "Default")
      (node (ref "u7") (pin "10") (pinfunction "IO25_10") (pintype "passive"))
    )
    (net (code "81") (name "unconnected-(u7-IO26-Pad11)") (class "Default")
      (node (ref "u7") (pin "11") (pinfunction "IO26_11") (pintype "passive"))
    )
    (net (code "82") (name "unconnected-(u7-IO27-Pad12)") (class "Default")
      (node (ref "u7") (pin "12") (pinfunction "IO27_12") (pintype "passive"))
    )
    (net (code "83") (name "unconnected-(u7-IO32-Pad8)") (class "Default")
      (node (ref "u7") (pin "8") (pinfunction "IO32_8") (pintype "passive"))
    )
    (net (code "84") (name "unconnected-(u7-IO33-Pad9)") (class "Default")
      (node (ref "u7") (pin "9") (pinfunction "IO33_9") (pintype "passive"))
    )
    (net (code "85") (name "unconnected-(u7-IO34-Pad6)") (class "Default")
      (node (ref "u7") (pin "6") (pinfunction "IO34_6") (pintype "passive"))
    )
    (net (code "86") (name "unconnected-(u7-IO35-Pad7)") (class "Default")
      (node (ref "u7") (pin "7") (pinfunction "IO35_7") (pintype "passive"))
    )
    (net (code "87") (name "unconnected-(u7-NC-Pad17)") (class "Default")
      (node (ref "u7") (pin "17") (pinfunction "NC_17") (pintype "passive"))
    )
    (net (code "88") (name "unconnected-(u7-NC-Pad18)") (class "Default")
      (node (ref "u7") (pin "18") (pinfunction "NC_18") (pintype "passive"))
    )
    (net (code "89") (name "unconnected-(u7-NC-Pad19)") (class "Default")
      (node (ref "u7") (pin "19") (pinfunction "NC_19") (pintype "passive"))
    )
    (net (code "90") (name "unconnected-(u7-NC-Pad20)") (class "Default")
      (node (ref "u7") (pin "20") (pinfunction "NC_20") (pintype "passive"))
    )
    (net (code "91") (name "unconnected-(u7-NC-Pad21)") (class "Default")
      (node (ref "u7") (pin "21") (pinfunction "NC_21") (pintype "passive"))
    )
    (net (code "92") (name "unconnected-(u7-NC-Pad22)") (class "Default")
      (node (ref "u7") (pin "22") (pinfunction "NC_22") (pintype "passive"))
    )
    (net (code "93") (name "unconnected-(u7-NC-Pad32)") (class "Default")
      (node (ref "u7") (pin "32") (pinfunction "NC_32") (pintype "passive"))
    )
    (net (code "94") (name "unconnected-(u7-SENSOR_VN-Pad5)") (class "Default")
      (node (ref "u7") (pin "5") (pinfunction "SENSOR_VN_5") (pintype "passive"))
    )
    (net (code "95") (name "unconnected-(u7-SENSOR_VP-Pad4)") (class "Default")
      (node (ref "u7") (pin "4") (pinfunction "SENSOR_VP_4") (pintype "passive"))
    )
  )
)
